# USB.net
KiCad netlist of a schematic drawn in Altium Designer
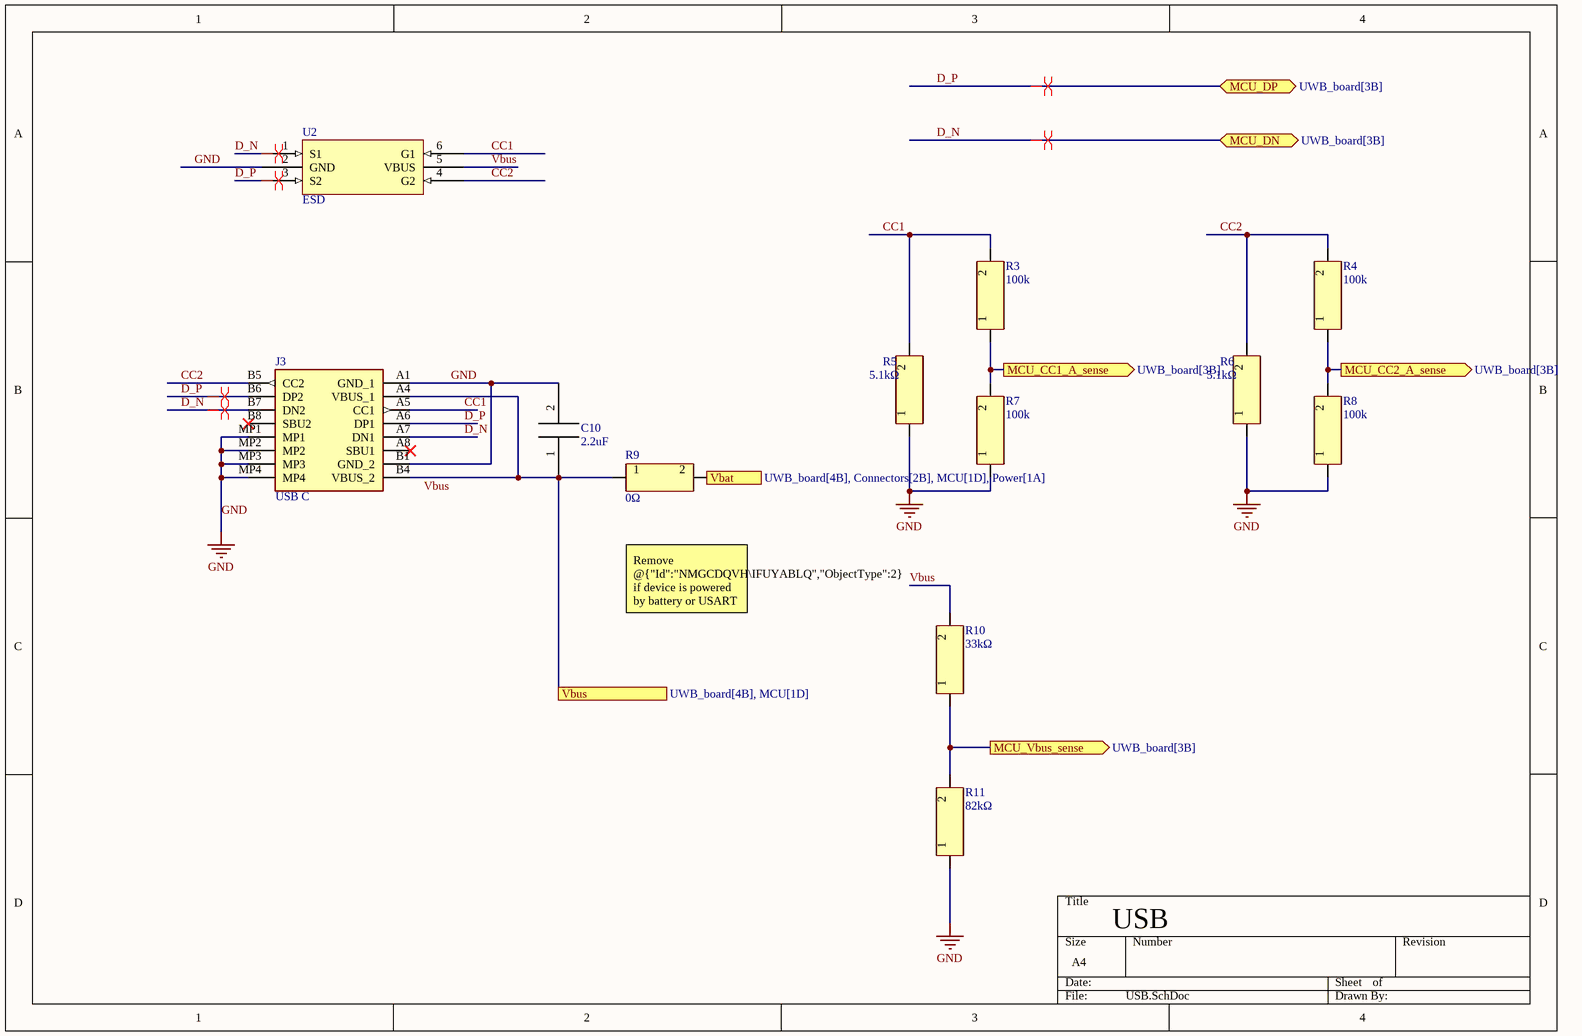
[diagram p0: USB.SchDoc]

(export (version "E")
  (design (tool "Eeschema 10.0.6"))
  (components
    (comp (ref "C10")
      (value "2.2uF")
      (footprint "0603_cap")
      (description "2.2uF 16V X5R ±10% 0603 Multilayer Ceramic Capacitors MLCC - SMD/SMT ROHS")
      (fields (field (name "LCSC PART #") "C23630"))
      (libsource (lib "Schlib1") (part "CL10A225KO8NNNC"))
    )
    (comp (ref "J3")
      (value "USB C")
      (footprint "UJ20CHGSMT5P16TR")
      (fields
        (field (name "MOUSER PART NUMBER") "179-UJ20CHGSMT5P16TR")
        (field (name "LCSC PART #") "C22383469")
      )
      (libsource (lib "Schlib1") (part "UJ20-C-H-G-SMT-5-P16-TR"))
    )
    (comp (ref "R3")
      (value "100k")
      (footprint "0603_res")
      (fields (field (name "LCSC PART #") "C25803"))
      (libsource (lib "Schlib1") (part "0603WAF1003T5E"))
    )
    (comp (ref "R4")
      (value "100k")
      (footprint "0603_res")
      (fields (field (name "LCSC PART #") "C25803"))
      (libsource (lib "Schlib1") (part "0603WAF1003T5E"))
    )
    (comp (ref "R5")
      (value "5.1kΩ")
      (footprint "0603_res")
      (fields (field (name "LCSC PART #") "C23186") (field (name "Comment") "5.1k"))
      (libsource (lib "Schlib1") (part "0603WAF5101T5E"))
    )
    (comp (ref "R6")
      (value "5.1kΩ")
      (footprint "0603_res")
      (fields (field (name "LCSC PART #") "C23186") (field (name "Comment") "5.1k"))
      (libsource (lib "Schlib1") (part "0603WAF5101T5E"))
    )
    (comp (ref "R7")
      (value "100k")
      (footprint "0603_res")
      (fields (field (name "LCSC PART #") "C25803"))
      (libsource (lib "Schlib1") (part "0603WAF1003T5E"))
    )
    (comp (ref "R8")
      (value "100k")
      (footprint "0603_res")
      (fields (field (name "LCSC PART #") "C25803"))
      (libsource (lib "Schlib1") (part "0603WAF1003T5E"))
    )
    (comp (ref "R9")
      (value "0Ω")
      (footprint "0603_res")
      (description "0Ω -55℃~+155℃ 100mW 75V Thick Film Resistor ±1% ±100ppm/℃ 0603 Chip Resistor - Surface Mount ROHS")
      (fields (field (name "LCSC PART #") "C21189") (field (name "Comment") "0R"))
      (libsource (lib "Schlib1") (part "0603WAF0000T5E"))
    )
    (comp (ref "R10")
      (value "33kΩ")
      (footprint "0603_res")
      (fields (field (name "LCSC PART #") "C4216") (field (name "Comment") "33k"))
      (libsource (lib "Schlib1") (part "0603WAF3302T5E"))
    )
    (comp (ref "R11")
      (value "82kΩ")
      (footprint "0603_res")
      (fields (field (name "LCSC PART #") "C23254") (field (name "Comment") "82k"))
      (libsource (lib "Schlib1") (part "0603WAF8202T5E"))
    )
    (comp (ref "U2")
      (value "ESD")
      (footprint "sot-23-6L_ESD")
      (fields (field (name "LCSC PART #") "C7420376"))
      (libsource (lib "Schlib1") (part "SRV05-4"))
    )
  )
  (nets
    (net (code "1") (name "/CC1") (class "Default")
      (node (ref "J3") (pin "A5") (pinfunction "CC1_A5") (pintype "output"))
      (node (ref "R3") (pin "2") (pinfunction "3_2") (pintype "passive"))
      (node (ref "R5") (pin "2") (pinfunction "3_2") (pintype "passive"))
      (node (ref "U2") (pin "6") (pinfunction "G1_6") (pintype "input"))
    )
    (net (code "2") (name "/CC2") (class "Default")
      (node (ref "J3") (pin "B5") (pinfunction "CC2_B5") (pintype "output"))
      (node (ref "R4") (pin "2") (pinfunction "3_2") (pintype "passive"))
      (node (ref "R6") (pin "2") (pinfunction "3_2") (pintype "passive"))
      (node (ref "U2") (pin "4") (pinfunction "G2_4") (pintype "input"))
    )
    (net (code "3") (name "/D_N") (class "Default")
      (node (ref "J3") (pin "A7") (pinfunction "DN1_A7") (pintype "passive"))
      (node (ref "J3") (pin "B7") (pinfunction "DN2_B7") (pintype "passive"))
      (node (ref "U2") (pin "1") (pinfunction "S1_1") (pintype "input"))
    )
    (net (code "4") (name "/D_P") (class "Default")
      (node (ref "J3") (pin "A6") (pinfunction "DP1_A6") (pintype "passive"))
      (node (ref "J3") (pin "B6") (pinfunction "DP2_B6") (pintype "passive"))
      (node (ref "U2") (pin "3") (pinfunction "S2_3") (pintype "input"))
    )
    (net (code "5") (name "/MCU_CC1_A_sense") (class "Default")
      (node (ref "R3") (pin "1") (pinfunction "1_1") (pintype "passive"))
      (node (ref "R7") (pin "2") (pinfunction "3_2") (pintype "passive"))
    )
    (net (code "6") (name "/MCU_CC2_A_sense") (class "Default")
      (node (ref "R4") (pin "1") (pinfunction "1_1") (pintype "passive"))
      (node (ref "R8") (pin "2") (pinfunction "3_2") (pintype "passive"))
    )
    (net (code "7") (name "/MCU_Vbus_sense") (class "Default")
      (node (ref "R10") (pin "1") (pinfunction "1_1") (pintype "passive"))
      (node (ref "R11") (pin "2") (pinfunction "3_2") (pintype "passive"))
    )
    (net (code "8") (name "/Vbat") (class "Default")
      (node (ref "R9") (pin "2") (pinfunction "3_2") (pintype "passive"))
    )
    (net (code "9") (name "/Vbus") (class "Default")
      (node (ref "C10") (pin "1") (pintype "passive"))
      (node (ref "J3") (pin "A4") (pinfunction "VBUS_1_A4") (pintype "passive"))
      (node (ref "J3") (pin "B4") (pinfunction "VBUS_2_B4") (pintype "passive"))
      (node (ref "R10") (pin "2") (pinfunction "3_2") (pintype "passive"))
      (node (ref "R9") (pin "1") (pinfunction "1_1") (pintype "passive"))
      (node (ref "U2") (pin "5") (pinfunction "VBUS_5") (pintype "power_in"))
    )
    (net (code "10") (name "GND") (class "Default")
      (node (ref "C10") (pin "2") (pinfunction "3_2") (pintype "passive"))
      (node (ref "J3") (pin "A1") (pinfunction "GND_1_A1") (pintype "passive"))
      (node (ref "J3") (pin "B1") (pinfunction "GND_2_B1") (pintype "passive"))
      (node (ref "J3") (pin "MP1") (pinfunction "MP1_MP1") (pintype "passive"))
      (node (ref "J3") (pin "MP2") (pinfunction "MP2_MP2") (pintype "passive"))
      (node (ref "J3") (pin "MP3") (pinfunction "MP3_MP3") (pintype "passive"))
      (node (ref "J3") (pin "MP4") (pinfunction "MP4_MP4") (pintype "passive"))
      (node (ref "R11") (pin "1") (pinfunction "1_1") (pintype "passive"))
      (node (ref "R5") (pin "1") (pinfunction "1_1") (pintype "passive"))
      (node (ref "R6") (pin "1") (pinfunction "1_1") (pintype "passive"))
      (node (ref "R7") (pin "1") (pinfunction "1_1") (pintype "passive"))
      (node (ref "R8") (pin "1") (pinfunction "1_1") (pintype "passive"))
      (node (ref "U2") (pin "2") (pinfunction "GND_2") (pintype "power_in"))
    )
    (net (code "11") (name "unconnected-(J3-SBU1-PadA8)") (class "Default")
      (node (ref "J3") (pin "A8") (pinfunction "SBU1_A8") (pintype "passive+no_connect"))
    )
    (net (code "12") (name "unconnected-(J3-SBU2-PadB8)") (class "Default")
      (node (ref "J3") (pin "B8") (pinfunction "SBU2_B8") (pintype "passive+no_connect"))
    )
  )
)
